# Sheet1.net
KiCad netlist of a schematic drawn in Altium Designer
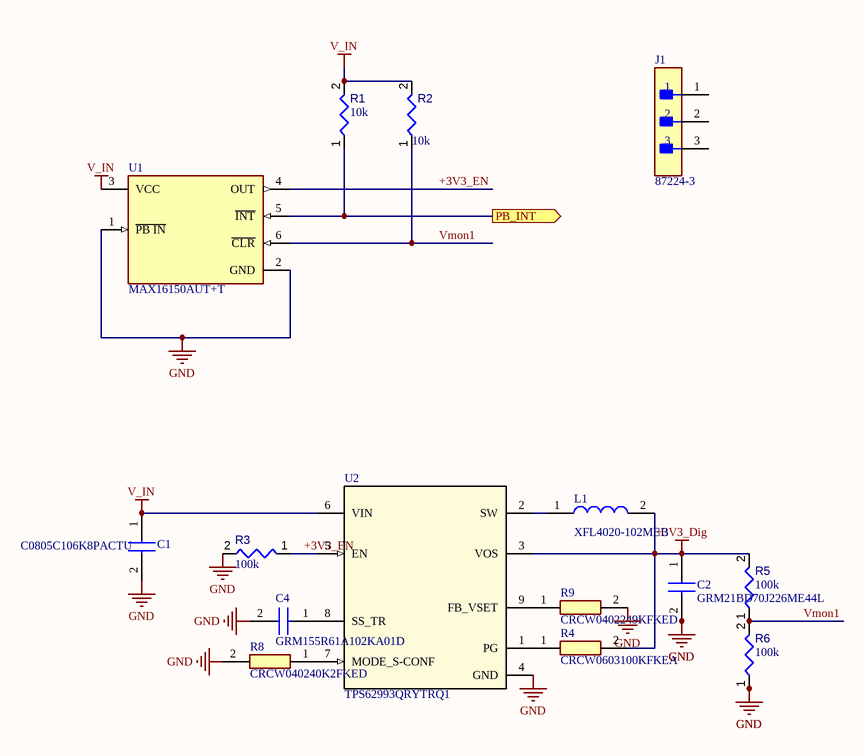
[diagram p0: Sheet1.SchDoc]

(export (version "E")
  (design (tool "Eeschema 10.0.6"))
  (components
    (comp (ref "C1")
      (value "C0805C106K8PACTU")
      (footprint "SamacSys:C0805")
      (description "Capacitor")
      (fields (field (name "MOUSER PART NUMBER") "80-C0805C106K8P"))
      (libsource (lib "*") (part "C0805C106K8PACTU"))
    )
    (comp (ref "C2")
      (value "GRM21BD70J226ME44L")
      (footprint "SamacSys:CAPC2012X145N")
      (description "Capacitor")
      (fields (field (name "MOUSER PART NUMBER") "81-GRM21BD70J226ME4L"))
      (libsource (lib "*") (part "GRM21BD70J226ME44L"))
    )
    (comp (ref "C4")
      (value "GRM155R61A102KA01D")
      (footprint "SamacSys:CAPC1005X55N")
      (description "Capacitor")
      (fields (field (name "MOUSER PART NUMBER") "81-GRM155R61A102KA1D"))
      (libsource (lib "*") (part "GRM155R61A102KA01D"))
    )
    (comp (ref "J1")
      (value "87224-3")
      (footprint "FP-87224-3-MFG")
      (description "CONN HEADER VERT 3POS 2.54MM")
      (libsource (lib "Altium Content Vault") (part "0d3f023dd272f625e17a2be33dea85f"))
    )
    (comp (ref "L1")
      (value "XFL4020-102MEB")
      (footprint "SamacSys:XFL4020102MEB")
      (description "Inductor")
      (fields (field (name "MOUSER PART NUMBER") "994-XFL4020-102MEB"))
      (libsource (lib "*") (part "XFL4020-102MEB"))
    )
    (comp (ref "R1")
      (value "10k")
      (footprint "RESC0402(1005)_L")
      (description "10K 0.063W 1% 0402 (1005 Metric)  SMD")
      (fields (field (name "POWER") "63mW") (field (name "TOLERANCE") "1%"))
      (libsource (lib "University of the Pacific") (part "10KR2F"))
    )
    (comp (ref "R2")
      (value "10k")
      (footprint "RESC0402(1005)_L")
      (description "10K 0.063W 1% 0402 (1005 Metric)  SMD")
      (fields (field (name "POWER") "63mW") (field (name "TOLERANCE") "1%"))
      (libsource (lib "University of the Pacific") (part "10KR2F"))
    )
    (comp (ref "R3")
      (value "100k")
      (footprint "RESC0402(1005)_L")
      (description "100K 0.063W 1% 0402 (1005 Metric)  SMD")
      (fields (field (name "POWER") "63mW") (field (name "TOLERANCE") "1%"))
      (libsource (lib "University of the Pacific") (part "100KR2F"))
    )
    (comp (ref "R4")
      (value "CRCW0603100KFKEA")
      (footprint "SamacSys:RESC1608X50N")
      (description "Resistor")
      (fields (field (name "MOUSER PART NUMBER") "71-CRCW0603-100K-E3"))
      (libsource (lib "*") (part "CRCW0603100KFKEA"))
    )
    (comp (ref "R5")
      (value "100k")
      (footprint "RESC0402(1005)_L")
      (description "100K 0.063W 1% 0402 (1005 Metric)  SMD")
      (fields (field (name "POWER") "63mW") (field (name "TOLERANCE") "1%"))
      (libsource (lib "University of the Pacific") (part "100KR2F"))
    )
    (comp (ref "R6")
      (value "100k")
      (footprint "RESC0402(1005)_L")
      (description "100K 0.063W 1% 0402 (1005 Metric)  SMD")
      (fields (field (name "POWER") "63mW") (field (name "TOLERANCE") "1%"))
      (libsource (lib "University of the Pacific") (part "100KR2F"))
    )
    (comp (ref "R8")
      (value "CRCW040240K2FKED")
      (footprint "SamacSys:RESC1005X40N")
      (description "Resistor")
      (fields (field (name "MOUSER PART NUMBER") "71-CRCW0402-40.2K-E3"))
      (libsource (lib "*") (part "CRCW040240K2FKED"))
    )
    (comp (ref "R9")
      (value "CRCW0402249KFKED")
      (footprint "SamacSys:RESC1005X40N")
      (description "Resistor")
      (fields (field (name "MOUSER PART NUMBER") "71-CRCW0402-249K-E3"))
      (libsource (lib "*") (part "CRCW0402249KFKED"))
    )
    (comp (ref "U1")
      (value "MAX16150AUT+T")
      (footprint "FP-U6-1-MFG")
      (description "IC SUPERVISOR 1 CHANNEL SOT23-6")
      (libsource (lib "Altium Content Vault") (part "36a392858d03d148bb8ce7f45f4b5f9"))
    )
    (comp (ref "U2")
      (value "TPS62993QRYTRQ1")
      (footprint "RYT0009A-MFG")
      (description "No Description Available")
      (fields (field (name "COPYRIGHT") "Copyright (C) 2023 Ultra Librarian. All rights reserved."))
      (libsource (lib "TPS62993QRYTRQ1") (part "TPS62993QRYTRQ1"))
    )
  )
  (nets
    (net (code "1") (name "+3V3_Dig") (class "Default")
      (node (ref "C2") (pin "1") (pinfunction "1_1") (pintype "passive"))
      (node (ref "L1") (pin "2") (pinfunction "2_2") (pintype "passive"))
      (node (ref "R4") (pin "2") (pinfunction "2_2") (pintype "passive"))
      (node (ref "R5") (pin "2") (pinfunction "2_2") (pintype "passive"))
      (node (ref "U2") (pin "3") (pinfunction "VOS_3") (pintype "passive"))
    )
    (net (code "2") (name "/+3V3_EN") (class "Default")
      (node (ref "R3") (pin "1") (pinfunction "1_1") (pintype "passive"))
      (node (ref "U1") (pin "4") (pinfunction "OUT_4") (pintype "output"))
      (node (ref "U2") (pin "5") (pinfunction "EN_5") (pintype "input"))
    )
    (net (code "4") (name "/PB_INT") (class "Default")
      (node (ref "R1") (pin "1") (pinfunction "1_1") (pintype "passive"))
      (node (ref "U1") (pin "5") (pinfunction "~{INT}_5") (pintype "input"))
    )
    (net (code "5") (name "/Vmon1") (class "Default")
      (node (ref "R2") (pin "1") (pinfunction "1_1") (pintype "passive"))
      (node (ref "R5") (pin "1") (pinfunction "1_1") (pintype "passive"))
      (node (ref "R6") (pin "2") (pinfunction "2_2") (pintype "passive"))
      (node (ref "U1") (pin "6") (pinfunction "~{CLR}_6") (pintype "input"))
    )
    (net (code "6") (name "GND") (class "Default")
      (node (ref "C1") (pin "2") (pinfunction "2_2") (pintype "passive"))
      (node (ref "C2") (pin "2") (pinfunction "2_2") (pintype "passive"))
      (node (ref "C4") (pin "2") (pinfunction "2_2") (pintype "passive"))
      (node (ref "R3") (pin "2") (pinfunction "2_2") (pintype "passive"))
      (node (ref "R6") (pin "1") (pinfunction "1_1") (pintype "passive"))
      (node (ref "R8") (pin "2") (pinfunction "2_2") (pintype "passive"))
      (node (ref "R9") (pin "2") (pinfunction "2_2") (pintype "passive"))
      (node (ref "U1") (pin "1") (pinfunction "~{PB_IN}_1") (pintype "input"))
      (node (ref "U1") (pin "2") (pinfunction "GND_2") (pintype "power_in"))
      (node (ref "U2") (pin "4") (pinfunction "GND_4") (pintype "power_in"))
    )
    (net (code "7") (name "Net-(U2-FB_VSET)") (class "Default")
      (node (ref "R9") (pin "1") (pinfunction "1_1") (pintype "passive"))
      (node (ref "U2") (pin "9") (pinfunction "FB_VSET_9") (pintype "passive"))
    )
    (net (code "8") (name "Net-(U2-MODE_S-CONF)") (class "Default")
      (node (ref "R8") (pin "1") (pinfunction "1_1") (pintype "passive"))
      (node (ref "U2") (pin "7") (pinfunction "MODE_S-CONF_7") (pintype "input"))
    )
    (net (code "9") (name "Net-(U2-PG)") (class "Default")
      (node (ref "R4") (pin "1") (pinfunction "1_1") (pintype "passive"))
      (node (ref "U2") (pin "1") (pinfunction "PG_1") (pintype "open_collector"))
    )
    (net (code "10") (name "Net-(U2-SS_TR)") (class "Default")
      (node (ref "C4") (pin "1") (pinfunction "1_1") (pintype "passive"))
      (node (ref "U2") (pin "8") (pinfunction "SS_TR_8") (pintype "passive"))
    )
    (net (code "11") (name "Net-(U2-SW)") (class "Default")
      (node (ref "L1") (pin "1") (pinfunction "1_1") (pintype "passive"))
      (node (ref "U2") (pin "2") (pinfunction "SW_2") (pintype "passive"))
    )
    (net (code "12") (name "V_IN") (class "Default")
      (node (ref "C1") (pin "1") (pinfunction "1_1") (pintype "passive"))
      (node (ref "R1") (pin "2") (pinfunction "2_2") (pintype "passive"))
      (node (ref "R2") (pin "2") (pinfunction "2_2") (pintype "passive"))
      (node (ref "U1") (pin "3") (pinfunction "VCC_3") (pintype "power_in"))
      (node (ref "U2") (pin "6") (pinfunction "VIN_6") (pintype "power_in"))
    )
    (net (code "13") (name "unconnected-(J1-Pad1)") (class "Default")
      (node (ref "J1") (pin "1") (pinfunction "1_1") (pintype "passive"))
    )
    (net (code "14") (name "unconnected-(J1-Pad2)") (class "Default")
      (node (ref "J1") (pin "2") (pinfunction "2_2") (pintype "passive"))
    )
    (net (code "15") (name "unconnected-(J1-Pad3)") (class "Default")
      (node (ref "J1") (pin "3") (pinfunction "3_3") (pintype "passive"))
    )
  )
)
